# 03_-_Decoders.net
KiCad netlist of a schematic drawn in Altium Designer
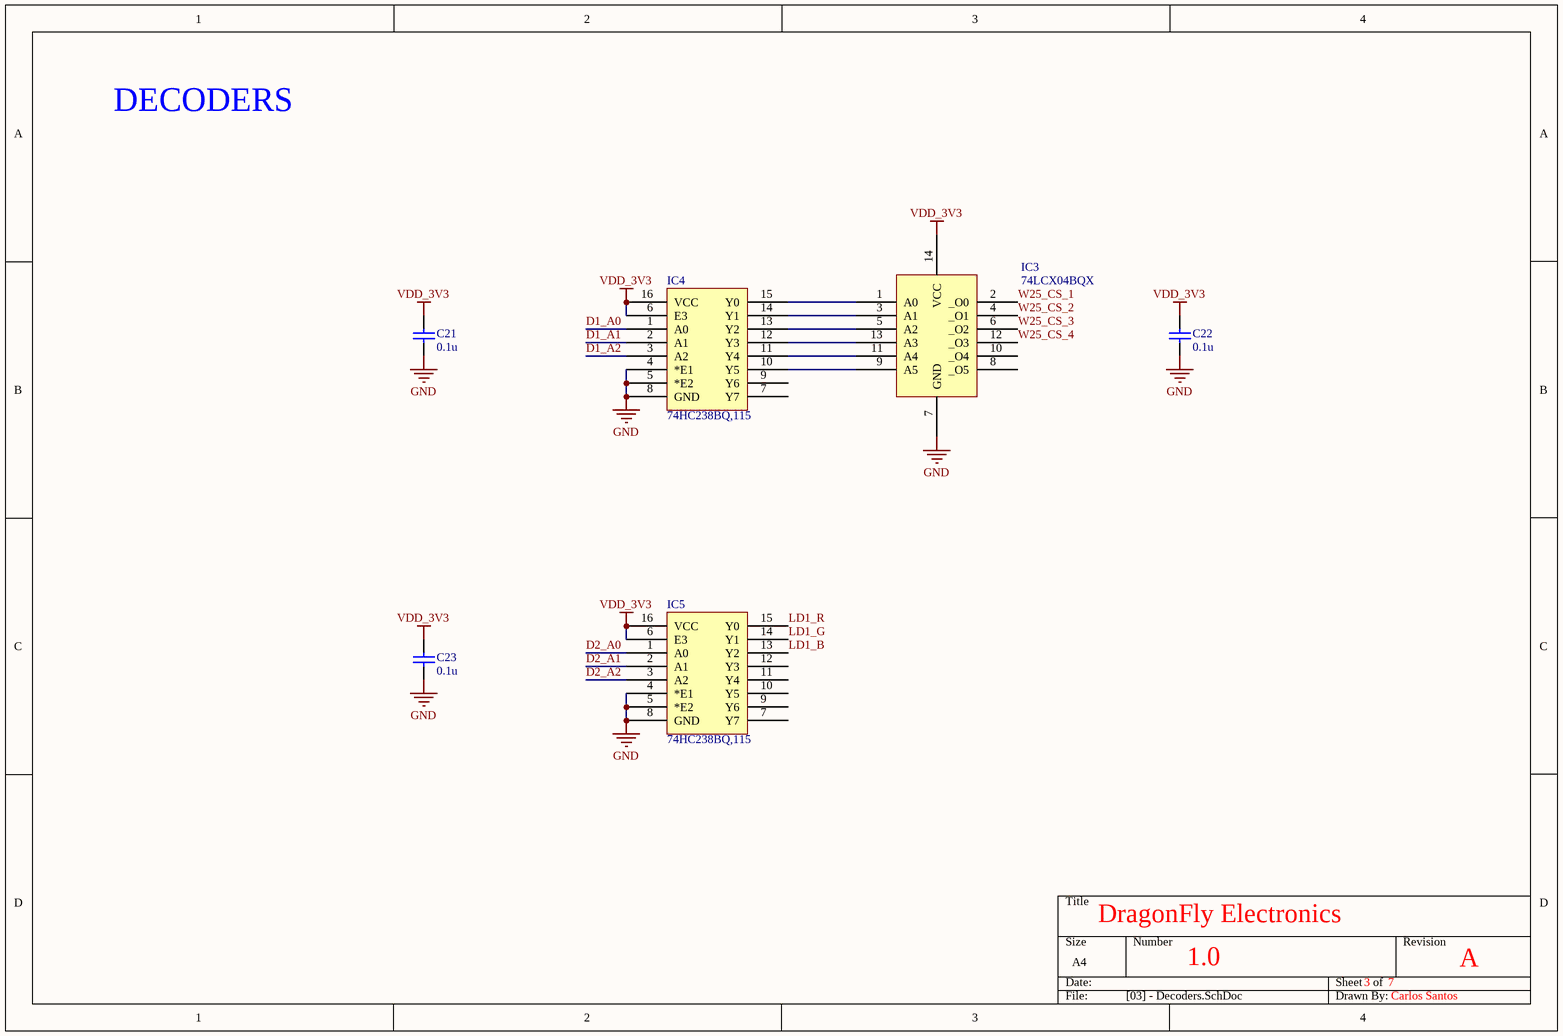
[diagram p0: [03] - Decoders.SchDoc]

(export (version "E")
  (design (tool "Eeschema 10.0.6"))
  (components
    (comp (ref "C21")
      (value "0.1u")
      (footprint "0402 - Capacitor")
      (fields (field (name "Comment") "Capacitor"))
      (libsource (lib "Mine") (part "Capacitor"))
    )
    (comp (ref "C22")
      (value "0.1u")
      (footprint "0402 - Capacitor")
      (fields (field (name "Comment") "Capacitor"))
      (libsource (lib "Mine") (part "Capacitor"))
    )
    (comp (ref "C23")
      (value "0.1u")
      (footprint "0402 - Capacitor")
      (fields (field (name "Comment") "Capacitor"))
      (libsource (lib "Mine") (part "Capacitor"))
    )
    (comp (ref "IC3")
      (value "74LCX04BQX")
      (footprint "74LCX04BQXFSCT - QFN")
      (fields (field (name "DIGIKEY PART #") "74LCX04BQXFSCT-ND"))
      (libsource (lib "Mine") (part "74LCX04BQX"))
    )
    (comp (ref "IC4")
      (value "74HC238BQ,115")
      (footprint "QFN127P600-8N")
      (fields (field (name "DIGIKEY PART #") "1727-6909-1-ND"))
      (libsource (lib "Mine") (part "74HC238BQ,115"))
    )
    (comp (ref "IC5")
      (value "74HC238BQ,115")
      (footprint "QFN127P600-8N")
      (fields (field (name "DIGIKEY PART #") "1727-6909-1-ND"))
      (libsource (lib "Mine") (part "74HC238BQ,115"))
    )
  )
  (nets
    (net (code "1") (name "/D1_A0") (class "Default")
      (node (ref "IC4") (pin "1") (pinfunction "A0_1") (pintype "passive"))
    )
    (net (code "2") (name "/D1_A1") (class "Default")
      (node (ref "IC4") (pin "2") (pinfunction "A1_2") (pintype "passive"))
    )
    (net (code "3") (name "/D1_A2") (class "Default")
      (node (ref "IC4") (pin "3") (pinfunction "A2_3") (pintype "passive"))
    )
    (net (code "4") (name "/D2_A0") (class "Default")
      (node (ref "IC5") (pin "1") (pinfunction "A0_1") (pintype "passive"))
    )
    (net (code "5") (name "/D2_A1") (class "Default")
      (node (ref "IC5") (pin "2") (pinfunction "A1_2") (pintype "passive"))
    )
    (net (code "6") (name "/D2_A2") (class "Default")
      (node (ref "IC5") (pin "3") (pinfunction "A2_3") (pintype "passive"))
    )
    (net (code "7") (name "/LD1_B") (class "Default")
      (node (ref "IC5") (pin "13") (pinfunction "Y2_13") (pintype "passive"))
    )
    (net (code "8") (name "/LD1_G") (class "Default")
      (node (ref "IC5") (pin "14") (pinfunction "Y1_14") (pintype "passive"))
    )
    (net (code "9") (name "/LD1_R") (class "Default")
      (node (ref "IC5") (pin "15") (pinfunction "Y0_15") (pintype "passive"))
    )
    (net (code "10") (name "/W25_CS_1") (class "Default")
      (node (ref "IC3") (pin "2") (pinfunction "_O0_2") (pintype "passive"))
    )
    (net (code "11") (name "/W25_CS_2") (class "Default")
      (node (ref "IC3") (pin "4") (pinfunction "_O1_4") (pintype "passive"))
    )
    (net (code "12") (name "/W25_CS_3") (class "Default")
      (node (ref "IC3") (pin "6") (pinfunction "_O2_6") (pintype "passive"))
    )
    (net (code "13") (name "/W25_CS_4") (class "Default")
      (node (ref "IC3") (pin "12") (pinfunction "_O3_12") (pintype "passive"))
    )
    (net (code "14") (name "GND") (class "Default")
      (node (ref "C21") (pin "1") (pinfunction "1_1") (pintype "passive"))
      (node (ref "C22") (pin "1") (pinfunction "1_1") (pintype "passive"))
      (node (ref "C23") (pin "1") (pinfunction "1_1") (pintype "passive"))
      (node (ref "IC3") (pin "7") (pinfunction "GND_7") (pintype "passive"))
      (node (ref "IC4") (pin "4") (pinfunction "*E1_4") (pintype "passive"))
      (node (ref "IC4") (pin "5") (pinfunction "*E2_5") (pintype "passive"))
      (node (ref "IC4") (pin "8") (pinfunction "GND_8") (pintype "passive"))
      (node (ref "IC5") (pin "4") (pinfunction "*E1_4") (pintype "passive"))
      (node (ref "IC5") (pin "5") (pinfunction "*E2_5") (pintype "passive"))
      (node (ref "IC5") (pin "8") (pinfunction "GND_8") (pintype "passive"))
    )
    (net (code "15") (name "Net-(IC3-A0)") (class "Default")
      (node (ref "IC3") (pin "1") (pinfunction "A0_1") (pintype "passive"))
      (node (ref "IC4") (pin "15") (pinfunction "Y0_15") (pintype "passive"))
    )
    (net (code "16") (name "Net-(IC3-A1)") (class "Default")
      (node (ref "IC3") (pin "3") (pinfunction "A1_3") (pintype "passive"))
      (node (ref "IC4") (pin "14") (pinfunction "Y1_14") (pintype "passive"))
    )
    (net (code "17") (name "Net-(IC3-A2)") (class "Default")
      (node (ref "IC3") (pin "5") (pinfunction "A2_5") (pintype "passive"))
      (node (ref "IC4") (pin "13") (pinfunction "Y2_13") (pintype "passive"))
    )
    (net (code "18") (name "Net-(IC3-A3)") (class "Default")
      (node (ref "IC3") (pin "13") (pinfunction "A3_13") (pintype "passive"))
      (node (ref "IC4") (pin "12") (pinfunction "Y3_12") (pintype "passive"))
    )
    (net (code "19") (name "Net-(IC3-A4)") (class "Default")
      (node (ref "IC3") (pin "11") (pinfunction "A4_11") (pintype "passive"))
      (node (ref "IC4") (pin "11") (pinfunction "Y4_11") (pintype "passive"))
    )
    (net (code "20") (name "Net-(IC3-A5)") (class "Default")
      (node (ref "IC3") (pin "9") (pinfunction "A5_9") (pintype "passive"))
      (node (ref "IC4") (pin "10") (pinfunction "Y5_10") (pintype "passive"))
    )
    (net (code "21") (name "VDD_3V3") (class "Default")
      (node (ref "C21") (pin "2") (pinfunction "2_2") (pintype "passive"))
      (node (ref "C22") (pin "2") (pinfunction "2_2") (pintype "passive"))
      (node (ref "C23") (pin "2") (pinfunction "2_2") (pintype "passive"))
      (node (ref "IC3") (pin "14") (pinfunction "VCC_14") (pintype "passive"))
      (node (ref "IC4") (pin "16") (pinfunction "VCC_16") (pintype "passive"))
      (node (ref "IC4") (pin "6") (pinfunction "E3_6") (pintype "passive"))
      (node (ref "IC5") (pin "16") (pinfunction "VCC_16") (pintype "passive"))
      (node (ref "IC5") (pin "6") (pinfunction "E3_6") (pintype "passive"))
    )
    (net (code "22") (name "unconnected-(IC3-_O4-Pad10)") (class "Default")
      (node (ref "IC3") (pin "10") (pinfunction "_O4_10") (pintype "passive"))
    )
    (net (code "23") (name "unconnected-(IC3-_O5-Pad8)") (class "Default")
      (node (ref "IC3") (pin "8") (pinfunction "_O5_8") (pintype "passive"))
    )
    (net (code "24") (name "unconnected-(IC4-Y6-Pad9)") (class "Default")
      (node (ref "IC4") (pin "9") (pinfunction "Y6_9") (pintype "passive"))
    )
    (net (code "25") (name "unconnected-(IC4-Y7-Pad7)") (class "Default")
      (node (ref "IC4") (pin "7") (pinfunction "Y7_7") (pintype "passive"))
    )
    (net (code "26") (name "unconnected-(IC5-Y3-Pad12)") (class "Default")
      (node (ref "IC5") (pin "12") (pinfunction "Y3_12") (pintype "passive"))
    )
    (net (code "27") (name "unconnected-(IC5-Y4-Pad11)") (class "Default")
      (node (ref "IC5") (pin "11") (pinfunction "Y4_11") (pintype "passive"))
    )
    (net (code "28") (name "unconnected-(IC5-Y5-Pad10)") (class "Default")
      (node (ref "IC5") (pin "10") (pinfunction "Y5_10") (pintype "passive"))
    )
    (net (code "29") (name "unconnected-(IC5-Y6-Pad9)") (class "Default")
      (node (ref "IC5") (pin "9") (pinfunction "Y6_9") (pintype "passive"))
    )
    (net (code "30") (name "unconnected-(IC5-Y7-Pad7)") (class "Default")
      (node (ref "IC5") (pin "7") (pinfunction "Y7_7") (pintype "passive"))
    )
  )
)
